# ICSL_PS_Combined_STM.net
KiCad netlist of a schematic drawn in Altium Designer
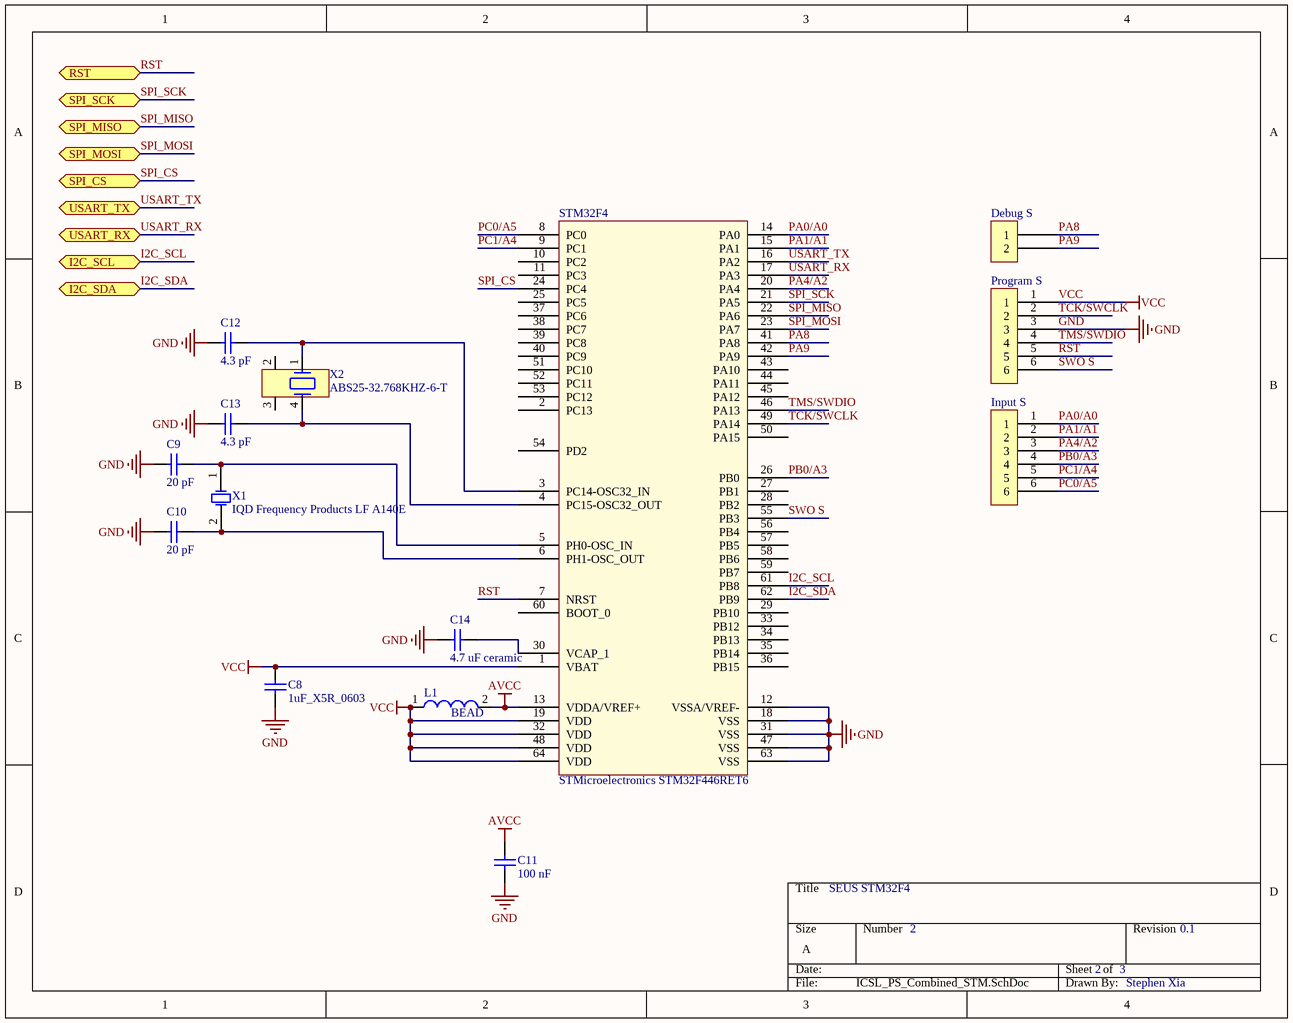
[diagram p0: ICSL_PS_Combined_STM.SchDoc]

(export (version "E")
  (design (tool "Eeschema 10.0.6"))
  (components
    (comp (ref "C8")
      (value "1uF_X5R_0603")
      (footprint "CAPC1608X87X35LL15T15")
      (description "Multilayer Ceramic Capacitors MLCC - SMD/SMT 50volts 82000pF X7R 10%")
      (libsource (lib "Octopart library") (part "CAP-2"))
    )
    (comp (ref "C9")
      (value "20 pF")
      (footprint "CAPC1608X87X35LL15T15")
      (description "Multilayer Ceramic Capacitors MLCC - SMD/SMT 50volts 82000pF X7R 10%")
      (libsource (lib "CommunityVault") (part "CMP-153056-3"))
    )
    (comp (ref "C10")
      (value "20 pF")
      (footprint "CAPC1608X87X35LL15T15")
      (description "Multilayer Ceramic Capacitors MLCC - SMD/SMT 50volts 82000pF X7R 10%")
      (libsource (lib "Octopart library") (part "CAP-2"))
    )
    (comp (ref "C11")
      (value "100 nF")
      (footprint "CAPC1608X87X35LL15T15")
      (description "Multilayer Ceramic Capacitors MLCC - SMD/SMT 50volts 82000pF X7R 10%")
      (libsource (lib "Octopart library") (part "CAP-2"))
    )
    (comp (ref "C12")
      (value "4.3 pF")
      (footprint "CAPC1608X87X35LL15T15")
      (description "Multilayer Ceramic Capacitors MLCC - SMD/SMT 50volts 82000pF X7R 10%")
      (libsource (lib "Octopart library") (part "CAP-2"))
    )
    (comp (ref "C13")
      (value "4.3 pF")
      (footprint "CAPC1608X87X35LL15T15")
      (description "Multilayer Ceramic Capacitors MLCC - SMD/SMT 50volts 82000pF X7R 10%")
      (libsource (lib "Octopart library") (part "CAP-2"))
    )
    (comp (ref "C14")
      (value "4.7 uF ceramic")
      (footprint "CAPC1608X87X35LL15T15")
      (description "Multilayer Ceramic Capacitors MLCC - SMD/SMT 50volts 82000pF X7R 10%")
      (libsource (lib "Octopart library") (part "CAP-2"))
    )
    (comp (ref "Debug S")
      (value "TE Connectivity / AMP 3-644695-2")
      (footprint "PCB-i8m17woc8q0u0fbeoczf-1")
      (description "Connector Unshrouded Header 2 Position 2.54mm Solder Straight Thru-Hole")
      (fields (field (name "MANUFACTURER PART NUMBER") "3-644695-2"))
      (libsource (lib "Octopart library") (part "SYM-2792ecc2f21af855-1"))
    )
    (comp (ref "Input S")
      (value "TE Connectivity / AMP 5-146281-6")
      (footprint "PCB-ceua2d6kgzjhmbkiz2sm-1")
      (description "Header; Breakaway; 0.100 in.; PC Board; Single; 6; 0.025 in.; 0.12 in.; 3 A")
      (fields (field (name "MANUFACTURER PART NUMBER") "5-146281-2"))
      (libsource (lib "Octopart library") (part "SYM-4f28847cfb2a90ef-1"))
    )
    (comp (ref "L1")
      (value "BEAD")
      (footprint "SMD-0402")
      (description "SMD EMI Suppression Ferrite Bead WE-CBF, Z = 800 Ohm")
      (libsource (lib "Octopart library") (part "PAS-IND-INDUCTOR-2"))
    )
    (comp (ref "Program S")
      (value "TE Connectivity / AMP 5-146281-6")
      (footprint "PCB-ceua2d6kgzjhmbkiz2sm-1")
      (description "Header; Breakaway; 0.100 in.; PC Board; Single; 6; 0.025 in.; 0.12 in.; 3 A")
      (fields (field (name "MANUFACTURER PART NUMBER") "5-146281-2"))
      (libsource (lib "Octopart library") (part "SYM-4f28847cfb2a90ef-1"))
    )
    (comp (ref "STM32F4")
      (value "STMicroelectronics STM32F446RET6")
      (footprint "TSQFP50P1200X1200X160-64N")
      (description "MCU 32-bit STM32 ARM Cortex M4 RISC 512KB Flash 2.5V/3.3V Medical 64-Pin LQFP Tray")
      (fields (field (name "MANUFACTURER PART NUMBER") "STM32F446RET6"))
      (libsource (lib "Octopart library") (part "SYM-ef3b25128e3530fc-1"))
    )
    (comp (ref "X1")
      (value "IQD Frequency Products LF A140E")
      (footprint "PCB-dsvehlm98b0q7gmbw6wh-1")
      (description "Crystal, Smd, 8mhz")
      (libsource (lib "Octopart library") (part "SYM-3d05f483ce79e2c2-1"))
    )
    (comp (ref "X2")
      (value "ABS25-32.768KHZ-6-T")
      (footprint "XTAL_4SM_8X3R8")
      (description "ABS25 Series 32.768 kHz ±20 ppm 6 pF -40 to +85 °C SMT Low Frequency Crystal")
      (libsource (lib "Octopart library") (part "XTAL_4P-4"))
    )
  )
  (nets
    (net (code "1") (name "/I2C_SCL") (class "Default")
      (node (ref "STM32F4") (pin "61") (pinfunction "PB8_61") (pintype "passive"))
    )
    (net (code "2") (name "/I2C_SDA") (class "Default")
      (node (ref "STM32F4") (pin "62") (pinfunction "PB9_62") (pintype "passive"))
    )
    (net (code "3") (name "/PA0{slash}A0") (class "Default")
      (node (ref "Input S") (pin "1") (pinfunction "1_1") (pintype "passive"))
      (node (ref "STM32F4") (pin "14") (pinfunction "PA0_14") (pintype "passive"))
    )
    (net (code "4") (name "/PA1{slash}A1") (class "Default")
      (node (ref "Input S") (pin "2") (pinfunction "2_2") (pintype "passive"))
      (node (ref "STM32F4") (pin "15") (pinfunction "PA1_15") (pintype "passive"))
    )
    (net (code "5") (name "/PA4{slash}A2") (class "Default")
      (node (ref "Input S") (pin "3") (pinfunction "3_3") (pintype "passive"))
      (node (ref "STM32F4") (pin "20") (pinfunction "PA4_20") (pintype "passive"))
    )
    (net (code "6") (name "/PA8") (class "Default")
      (node (ref "Debug S") (pin "1") (pinfunction "1_1") (pintype "passive"))
      (node (ref "STM32F4") (pin "41") (pinfunction "PA8_41") (pintype "passive"))
    )
    (net (code "7") (name "/PA9") (class "Default")
      (node (ref "Debug S") (pin "2") (pinfunction "2_2") (pintype "passive"))
      (node (ref "STM32F4") (pin "42") (pinfunction "PA9_42") (pintype "passive"))
    )
    (net (code "8") (name "/PB0{slash}A3") (class "Default")
      (node (ref "Input S") (pin "4") (pinfunction "4_4") (pintype "passive"))
      (node (ref "STM32F4") (pin "26") (pinfunction "PB0_26") (pintype "passive"))
    )
    (net (code "9") (name "/PC0{slash}A5") (class "Default")
      (node (ref "Input S") (pin "6") (pinfunction "6_6") (pintype "passive"))
      (node (ref "STM32F4") (pin "8") (pinfunction "PC0_8") (pintype "passive"))
    )
    (net (code "10") (name "/PC1{slash}A4") (class "Default")
      (node (ref "Input S") (pin "5") (pinfunction "5_5") (pintype "passive"))
      (node (ref "STM32F4") (pin "9") (pinfunction "PC1_9") (pintype "passive"))
    )
    (net (code "11") (name "/RST") (class "Default")
      (node (ref "Program S") (pin "5") (pinfunction "5_5") (pintype "passive"))
      (node (ref "STM32F4") (pin "7") (pinfunction "NRST_7") (pintype "passive"))
    )
    (net (code "12") (name "/SPI_CS") (class "Default")
      (node (ref "STM32F4") (pin "24") (pinfunction "PC4_24") (pintype "passive"))
    )
    (net (code "13") (name "/SPI_MISO") (class "Default")
      (node (ref "STM32F4") (pin "22") (pinfunction "PA6_22") (pintype "passive"))
    )
    (net (code "14") (name "/SPI_MOSI") (class "Default")
      (node (ref "STM32F4") (pin "23") (pinfunction "PA7_23") (pintype "passive"))
    )
    (net (code "15") (name "/SPI_SCK") (class "Default")
      (node (ref "STM32F4") (pin "21") (pinfunction "PA5_21") (pintype "passive"))
    )
    (net (code "16") (name "/SWO S") (class "Default")
      (node (ref "Program S") (pin "6") (pinfunction "6_6") (pintype "passive"))
      (node (ref "STM32F4") (pin "55") (pinfunction "PB3_55") (pintype "passive"))
    )
    (net (code "17") (name "/TCK{slash}SWCLK") (class "Default")
      (node (ref "Program S") (pin "2") (pinfunction "2_2") (pintype "passive"))
      (node (ref "STM32F4") (pin "49") (pinfunction "PA14_49") (pintype "passive"))
    )
    (net (code "18") (name "/TMS{slash}SWDIO") (class "Default")
      (node (ref "Program S") (pin "4") (pinfunction "4_4") (pintype "passive"))
      (node (ref "STM32F4") (pin "46") (pinfunction "PA13_46") (pintype "passive"))
    )
    (net (code "19") (name "/USART_RX") (class "Default")
      (node (ref "STM32F4") (pin "17") (pinfunction "PA3_17") (pintype "passive"))
    )
    (net (code "20") (name "/USART_TX") (class "Default")
      (node (ref "STM32F4") (pin "16") (pinfunction "PA2_16") (pintype "passive"))
    )
    (net (code "21") (name "AVCC") (class "Default")
      (node (ref "C11") (pin "2") (pinfunction "2_2") (pintype "passive"))
      (node (ref "L1") (pin "2") (pinfunction "2_2") (pintype "passive"))
      (node (ref "STM32F4") (pin "13") (pinfunction "VDDA/VREF+_13") (pintype "passive"))
    )
    (net (code "22") (name "GND") (class "Default")
      (node (ref "C10") (pin "2") (pinfunction "2_2") (pintype "passive"))
      (node (ref "C11") (pin "1") (pinfunction "1_1") (pintype "passive"))
      (node (ref "C12") (pin "2") (pinfunction "2_2") (pintype "passive"))
      (node (ref "C13") (pin "2") (pinfunction "2_2") (pintype "passive"))
      (node (ref "C14") (pin "2") (pinfunction "2_2") (pintype "passive"))
      (node (ref "C8") (pin "1") (pinfunction "1_1") (pintype "passive"))
      (node (ref "C9") (pin "2") (pinfunction "2_2") (pintype "passive"))
      (node (ref "Program S") (pin "3") (pinfunction "3_3") (pintype "passive"))
      (node (ref "STM32F4") (pin "12") (pinfunction "VSSA/VREF-_12") (pintype "passive"))
      (node (ref "STM32F4") (pin "18") (pinfunction "VSS_18") (pintype "passive"))
      (node (ref "STM32F4") (pin "31") (pinfunction "VSS_31") (pintype "passive"))
      (node (ref "STM32F4") (pin "47") (pinfunction "VSS_47") (pintype "passive"))
      (node (ref "STM32F4") (pin "63") (pinfunction "VSS_63") (pintype "passive"))
    )
    (net (code "23") (name "Net-(STM32F4-PC14-OSC32_IN)") (class "Default")
      (node (ref "C12") (pin "1") (pinfunction "1_1") (pintype "passive"))
      (node (ref "STM32F4") (pin "3") (pinfunction "PC14-OSC32_IN_3") (pintype "passive"))
      (node (ref "X2") (pin "1") (pinfunction "1_1") (pintype "passive"))
    )
    (net (code "24") (name "Net-(STM32F4-PC15-OSC32_OUT)") (class "Default")
      (node (ref "C13") (pin "1") (pinfunction "1_1") (pintype "passive"))
      (node (ref "STM32F4") (pin "4") (pinfunction "PC15-OSC32_OUT_4") (pintype "passive"))
      (node (ref "X2") (pin "4") (pinfunction "4_4") (pintype "passive"))
    )
    (net (code "25") (name "Net-(STM32F4-PH0-OSC_IN)") (class "Default")
      (node (ref "C9") (pin "1") (pinfunction "1_1") (pintype "passive"))
      (node (ref "STM32F4") (pin "5") (pinfunction "PH0-OSC_IN_5") (pintype "passive"))
      (node (ref "X1") (pin "1") (pinfunction "X1_1") (pintype "passive"))
    )
    (net (code "26") (name "Net-(STM32F4-PH1-OSC_OUT)") (class "Default")
      (node (ref "C10") (pin "1") (pinfunction "1_1") (pintype "passive"))
      (node (ref "STM32F4") (pin "6") (pinfunction "PH1-OSC_OUT_6") (pintype "passive"))
      (node (ref "X1") (pin "2") (pinfunction "X2_2") (pintype "passive"))
    )
    (net (code "27") (name "Net-(STM32F4-VCAP_1)") (class "Default")
      (node (ref "C14") (pin "1") (pinfunction "1_1") (pintype "passive"))
      (node (ref "STM32F4") (pin "30") (pinfunction "VCAP_1_30") (pintype "passive"))
    )
    (net (code "28") (name "VCC") (class "Default")
      (node (ref "C8") (pin "2") (pinfunction "2_2") (pintype "passive"))
      (node (ref "L1") (pin "1") (pinfunction "1_1") (pintype "passive"))
      (node (ref "Program S") (pin "1") (pinfunction "1_1") (pintype "passive"))
      (node (ref "STM32F4") (pin "1") (pinfunction "VBAT_1") (pintype "passive"))
      (node (ref "STM32F4") (pin "19") (pinfunction "VDD_19") (pintype "passive"))
      (node (ref "STM32F4") (pin "32") (pinfunction "VDD_32") (pintype "passive"))
      (node (ref "STM32F4") (pin "48") (pinfunction "VDD_48") (pintype "passive"))
      (node (ref "STM32F4") (pin "64") (pinfunction "VDD_64") (pintype "passive"))
    )
    (net (code "29") (name "unconnected-(STM32F4-BOOT_0-Pad60)") (class "Default")
      (node (ref "STM32F4") (pin "60") (pinfunction "BOOT_0_60") (pintype "passive"))
    )
    (net (code "30") (name "unconnected-(STM32F4-PA10-Pad43)") (class "Default")
      (node (ref "STM32F4") (pin "43") (pinfunction "PA10_43") (pintype "passive"))
    )
    (net (code "31") (name "unconnected-(STM32F4-PA11-Pad44)") (class "Default")
      (node (ref "STM32F4") (pin "44") (pinfunction "PA11_44") (pintype "passive"))
    )
    (net (code "32") (name "unconnected-(STM32F4-PA12-Pad45)") (class "Default")
      (node (ref "STM32F4") (pin "45") (pinfunction "PA12_45") (pintype "passive"))
    )
    (net (code "33") (name "unconnected-(STM32F4-PA15-Pad50)") (class "Default")
      (node (ref "STM32F4") (pin "50") (pinfunction "PA15_50") (pintype "passive"))
    )
    (net (code "34") (name "unconnected-(STM32F4-PB1-Pad27)") (class "Default")
      (node (ref "STM32F4") (pin "27") (pinfunction "PB1_27") (pintype "passive"))
    )
    (net (code "35") (name "unconnected-(STM32F4-PB2-Pad28)") (class "Default")
      (node (ref "STM32F4") (pin "28") (pinfunction "PB2_28") (pintype "passive"))
    )
    (net (code "36") (name "unconnected-(STM32F4-PB4-Pad56)") (class "Default")
      (node (ref "STM32F4") (pin "56") (pinfunction "PB4_56") (pintype "passive"))
    )
    (net (code "37") (name "unconnected-(STM32F4-PB5-Pad57)") (class "Default")
      (node (ref "STM32F4") (pin "57") (pinfunction "PB5_57") (pintype "passive"))
    )
    (net (code "38") (name "unconnected-(STM32F4-PB6-Pad58)") (class "Default")
      (node (ref "STM32F4") (pin "58") (pinfunction "PB6_58") (pintype "passive"))
    )
    (net (code "39") (name "unconnected-(STM32F4-PB7-Pad59)") (class "Default")
      (node (ref "STM32F4") (pin "59") (pinfunction "PB7_59") (pintype "passive"))
    )
    (net (code "40") (name "unconnected-(STM32F4-PB10-Pad29)") (class "Default")
      (node (ref "STM32F4") (pin "29") (pinfunction "PB10_29") (pintype "passive"))
    )
    (net (code "41") (name "unconnected-(STM32F4-PB12-Pad33)") (class "Default")
      (node (ref "STM32F4") (pin "33") (pinfunction "PB12_33") (pintype "passive"))
    )
    (net (code "42") (name "unconnected-(STM32F4-PB13-Pad34)") (class "Default")
      (node (ref "STM32F4") (pin "34") (pinfunction "PB13_34") (pintype "passive"))
    )
    (net (code "43") (name "unconnected-(STM32F4-PB14-Pad35)") (class "Default")
      (node (ref "STM32F4") (pin "35") (pinfunction "PB14_35") (pintype "passive"))
    )
    (net (code "44") (name "unconnected-(STM32F4-PB15-Pad36)") (class "Default")
      (node (ref "STM32F4") (pin "36") (pinfunction "PB15_36") (pintype "passive"))
    )
    (net (code "45") (name "unconnected-(STM32F4-PC2-Pad10)") (class "Default")
      (node (ref "STM32F4") (pin "10") (pinfunction "PC2_10") (pintype "passive"))
    )
    (net (code "46") (name "unconnected-(STM32F4-PC3-Pad11)") (class "Default")
      (node (ref "STM32F4") (pin "11") (pinfunction "PC3_11") (pintype "passive"))
    )
    (net (code "47") (name "unconnected-(STM32F4-PC5-Pad25)") (class "Default")
      (node (ref "STM32F4") (pin "25") (pinfunction "PC5_25") (pintype "passive"))
    )
    (net (code "48") (name "unconnected-(STM32F4-PC6-Pad37)") (class "Default")
      (node (ref "STM32F4") (pin "37") (pinfunction "PC6_37") (pintype "passive"))
    )
    (net (code "49") (name "unconnected-(STM32F4-PC7-Pad38)") (class "Default")
      (node (ref "STM32F4") (pin "38") (pinfunction "PC7_38") (pintype "passive"))
    )
    (net (code "50") (name "unconnected-(STM32F4-PC8-Pad39)") (class "Default")
      (node (ref "STM32F4") (pin "39") (pinfunction "PC8_39") (pintype "passive"))
    )
    (net (code "51") (name "unconnected-(STM32F4-PC9-Pad40)") (class "Default")
      (node (ref "STM32F4") (pin "40") (pinfunction "PC9_40") (pintype "passive"))
    )
    (net (code "52") (name "unconnected-(STM32F4-PC10-Pad51)") (class "Default")
      (node (ref "STM32F4") (pin "51") (pinfunction "PC10_51") (pintype "passive"))
    )
    (net (code "53") (name "unconnected-(STM32F4-PC11-Pad52)") (class "Default")
      (node (ref "STM32F4") (pin "52") (pinfunction "PC11_52") (pintype "passive"))
    )
    (net (code "54") (name "unconnected-(STM32F4-PC12-Pad53)") (class "Default")
      (node (ref "STM32F4") (pin "53") (pinfunction "PC12_53") (pintype "passive"))
    )
    (net (code "55") (name "unconnected-(STM32F4-PC13-Pad2)") (class "Default")
      (node (ref "STM32F4") (pin "2") (pinfunction "PC13_2") (pintype "passive"))
    )
    (net (code "56") (name "unconnected-(STM32F4-PD2-Pad54)") (class "Default")
      (node (ref "STM32F4") (pin "54") (pinfunction "PD2_54") (pintype "passive"))
    )
    (net (code "57") (name "unconnected-(X2-Pad2)") (class "Default")
      (node (ref "X2") (pin "2") (pinfunction "2_2") (pintype "passive"))
    )
    (net (code "58") (name "unconnected-(X2-Pad3)") (class "Default")
      (node (ref "X2") (pin "3") (pinfunction "3_3") (pintype "passive"))
    )
  )
)
